# 5V-to-12V-Converter-alt2.net
KiCad netlist of a schematic drawn in EAGLE
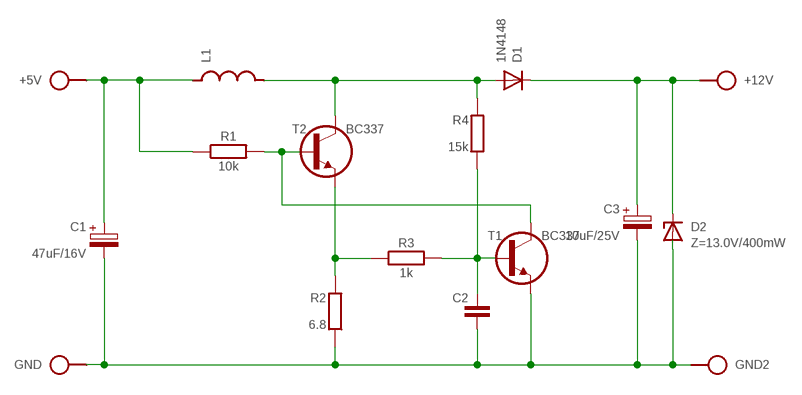
[diagram p0: schematic, sheet 1]

(export (version "E")
  (design (tool "Eeschema 10.0.6"))
  (components
    (comp (ref "+5V")
      (value "SPAD")
      (footprint "eagle-import:SPAD")
      (libsource (lib "eagle-import") (part "SPAD"))
    )
    (comp (ref "+12V")
      (value "SPAD")
      (footprint "eagle-import:SPAD")
      (libsource (lib "eagle-import") (part "SPAD"))
    )
    (comp (ref "C1")
      (value "47uF/16V")
      (footprint "eagle-import:E2.5-4_V")
      (libsource (lib "eagle-import") (part "CPOLE2,5-4/V"))
    )
    (comp (ref "C2")
      (value "C050-025X075")
      (footprint "eagle-import:C050-025X075")
      (libsource (lib "eagle-import") (part "C050-025X075"))
    )
    (comp (ref "C3")
      (value "10uF/25V")
      (footprint "eagle-import:E2.5-4_V")
      (libsource (lib "eagle-import") (part "CPOLE2,5-4/V"))
    )
    (comp (ref "D1")
      (value "1N4148")
      (footprint "eagle-import:DO34-7")
      (libsource (lib "eagle-import") (part "1N414834-7"))
    )
    (comp (ref "D2")
      (value "Z=13.0V/400mW")
      (footprint "eagle-import:DO34Z10V")
      (libsource (lib "eagle-import") (part "Z-DIODE34Z10V"))
    )
    (comp (ref "GND")
      (value "SPAD")
      (footprint "eagle-import:SPAD")
      (libsource (lib "eagle-import") (part "SPAD"))
    )
    (comp (ref "GND2")
      (value "SPAD")
      (footprint "eagle-import:SPAD")
      (libsource (lib "eagle-import") (part "SPAD"))
    )
    (comp (ref "L1")
      (value "L-SHORT02/5")
      (footprint "eagle-import:L-02_5V")
      (libsource (lib "eagle-import") (part "L-SHORT02/5"))
    )
    (comp (ref "R1")
      (value "10k")
      (footprint "eagle-import:0204_10")
      (libsource (lib "eagle-import") (part "R-H0204/10"))
    )
    (comp (ref "R2")
      (value "6.8")
      (footprint "eagle-import:0204_10")
      (libsource (lib "eagle-import") (part "R0204/10"))
    )
    (comp (ref "R3")
      (value "1k")
      (footprint "eagle-import:0204_10")
      (libsource (lib "eagle-import") (part "R-H0204/10"))
    )
    (comp (ref "R4")
      (value "15k")
      (footprint "eagle-import:0204_10")
      (libsource (lib "eagle-import") (part "R0204/10"))
    )
    (comp (ref "T1")
      (value "BC337")
      (footprint "eagle-import:TO92-CBE")
      (libsource (lib "eagle-import") (part "BC337CBE"))
    )
    (comp (ref "T2")
      (value "BC337")
      (footprint "eagle-import:TO92-CBE")
      (libsource (lib "eagle-import") (part "BC337CBE"))
    )
  )
  (nets
    (net (code "1") (name "Net-(+5V-P$1)") (class "Default")
      (node (ref "+5V") (pin "1") (pinfunction "P$1_1") (pintype "passive"))
      (node (ref "C1") (pin "+") (pinfunction "+_+") (pintype "passive"))
      (node (ref "L1") (pin "2") (pinfunction "2_2") (pintype "passive"))
      (node (ref "R1") (pin "1") (pinfunction "1_1") (pintype "passive"))
    )
    (net (code "2") (name "Net-(+12V-P$1)") (class "Default")
      (node (ref "+12V") (pin "1") (pinfunction "P$1_1") (pintype "passive"))
      (node (ref "C3") (pin "+") (pinfunction "+_+") (pintype "passive"))
      (node (ref "D1") (pin "C") (pinfunction "C_C") (pintype "passive"))
      (node (ref "D2") (pin "C") (pinfunction "C_C") (pintype "passive"))
    )
    (net (code "3") (name "Net-(GND-P$1)") (class "Default")
      (node (ref "C1") (pin "-") (pinfunction "-_-") (pintype "passive"))
      (node (ref "C2") (pin "2") (pinfunction "2_2") (pintype "passive"))
      (node (ref "C3") (pin "-") (pinfunction "-_-") (pintype "passive"))
      (node (ref "D2") (pin "A") (pinfunction "A_A") (pintype "passive"))
      (node (ref "GND") (pin "1") (pinfunction "P$1_1") (pintype "passive"))
      (node (ref "GND2") (pin "1") (pinfunction "P$1_1") (pintype "passive"))
      (node (ref "R2") (pin "1") (pinfunction "2_1") (pintype "passive"))
      (node (ref "T1") (pin "E") (pinfunction "E_E") (pintype "passive"))
    )
    (net (code "4") (name "Net-(R1-Pad2)") (class "Default")
      (node (ref "R1") (pin "2") (pinfunction "2_2") (pintype "passive"))
      (node (ref "T1") (pin "C") (pinfunction "C_C") (pintype "passive"))
      (node (ref "T2") (pin "B") (pinfunction "B_B") (pintype "passive"))
    )
    (net (code "5") (name "Net-(R2-1)") (class "Default")
      (node (ref "R2") (pin "2") (pinfunction "1_2") (pintype "passive"))
      (node (ref "R3") (pin "1") (pinfunction "1_1") (pintype "passive"))
      (node (ref "T2") (pin "E") (pinfunction "E_E") (pintype "passive"))
    )
    (net (code "6") (name "Net-(R4-1)") (class "Default")
      (node (ref "D1") (pin "A") (pinfunction "A_A") (pintype "passive"))
      (node (ref "L1") (pin "1") (pinfunction "1_1") (pintype "passive"))
      (node (ref "R4") (pin "2") (pinfunction "1_2") (pintype "passive"))
      (node (ref "T2") (pin "C") (pinfunction "C_C") (pintype "passive"))
    )
    (net (code "7") (name "Net-(R4-2)") (class "Default")
      (node (ref "C2") (pin "1") (pinfunction "1_1") (pintype "passive"))
      (node (ref "R3") (pin "2") (pinfunction "2_2") (pintype "passive"))
      (node (ref "R4") (pin "1") (pinfunction "2_1") (pintype "passive"))
      (node (ref "T1") (pin "B") (pinfunction "B_B") (pintype "passive"))
    )
  )
)
